# Output.net
KiCad netlist of a schematic drawn in EAGLE
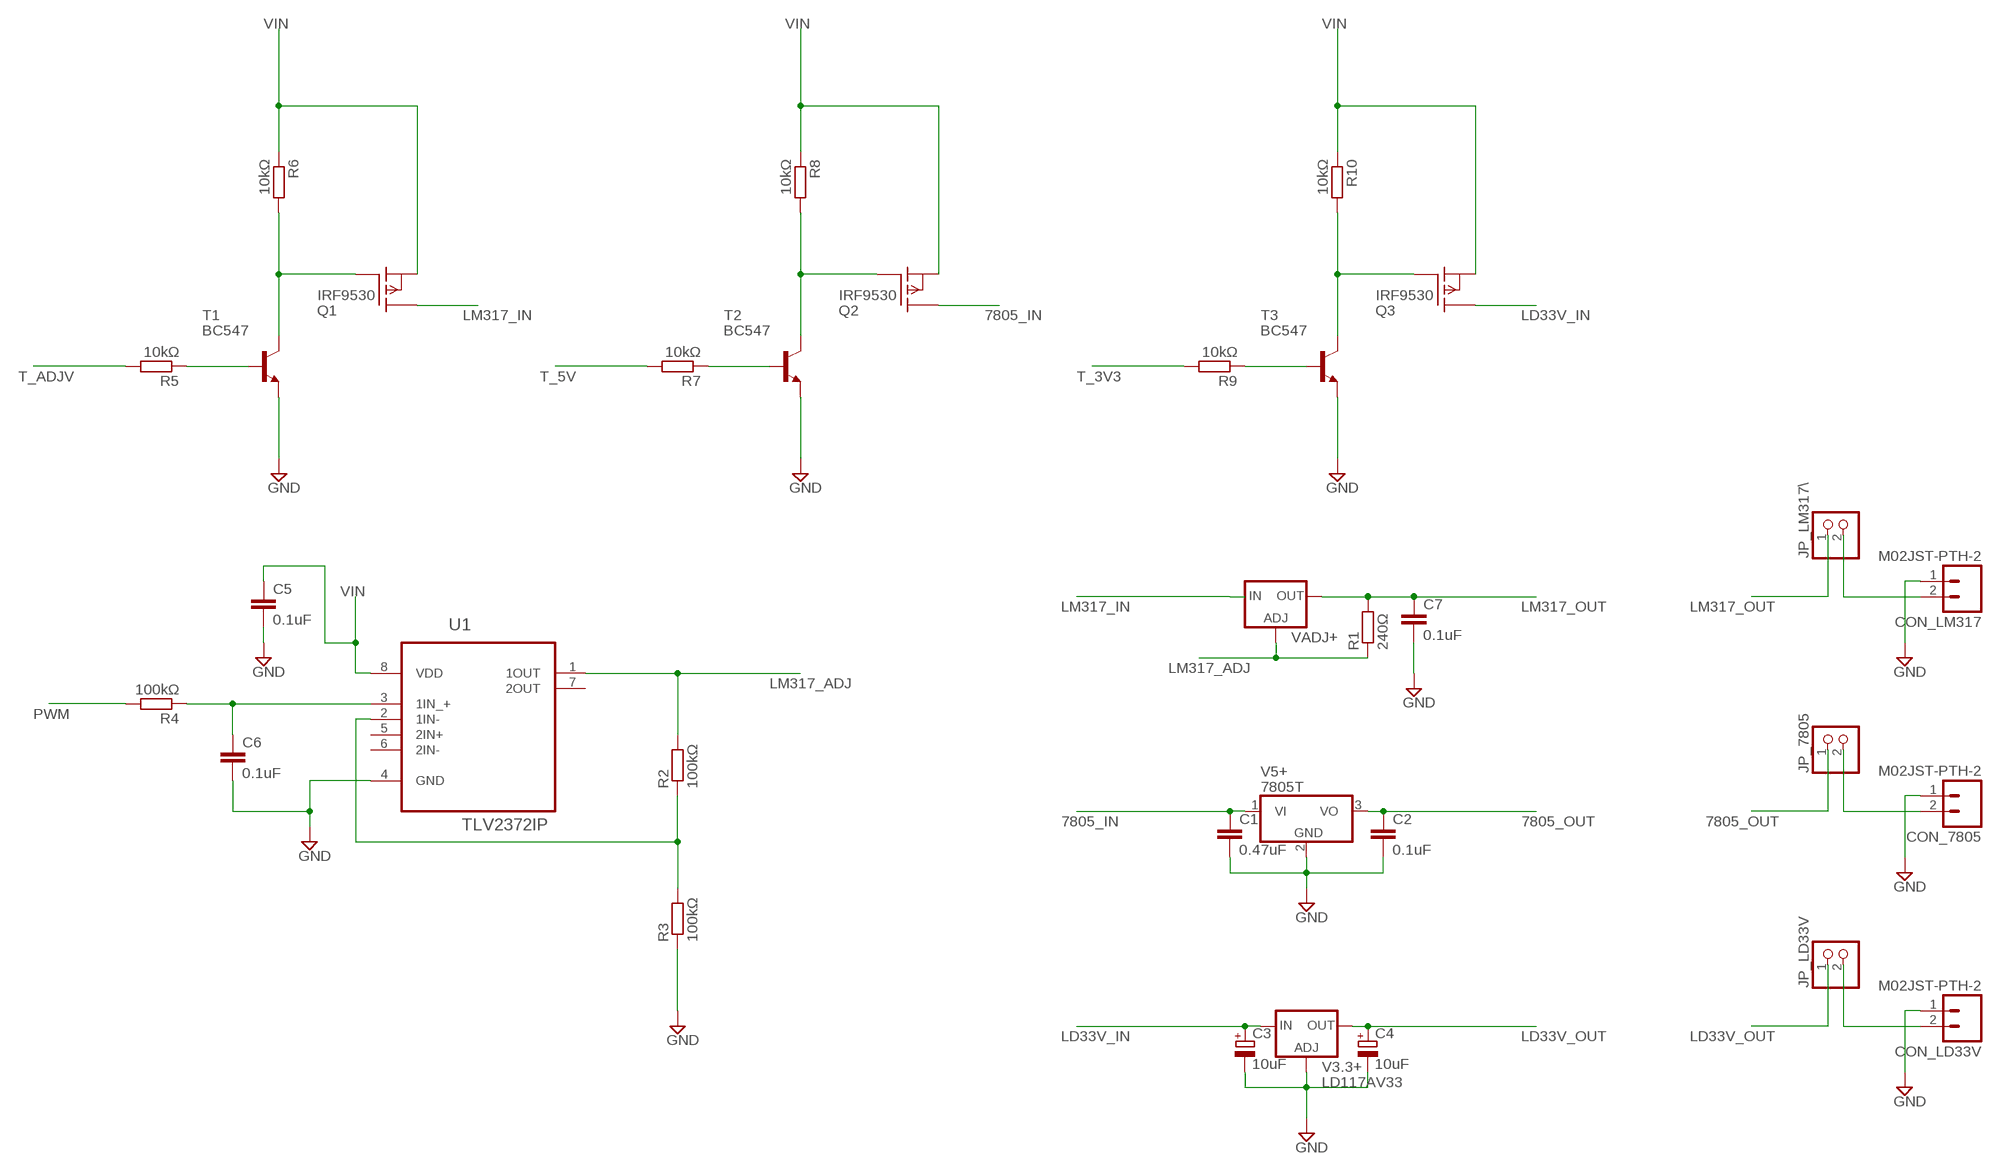
[diagram p0: schematic, sheet 1]

(export (version "E")
  (design (tool "Eeschema 10.0.6"))
  (components
    (comp (ref "C1")
      (value "0.47uF")
      (footprint "eagle-import:C025-025X050")
      (libsource (lib "eagle-import") (part "C-EU025-025X050"))
    )
    (comp (ref "C2")
      (value "0.1uF")
      (footprint "eagle-import:C025-025X050")
      (libsource (lib "eagle-import") (part "C-EU025-025X050"))
    )
    (comp (ref "C3")
      (value "10uF")
      (footprint "eagle-import:E2,5-6")
      (libsource (lib "eagle-import") (part "CPOL-EUE2.5-6"))
    )
    (comp (ref "C4")
      (value "10uF")
      (footprint "eagle-import:E2,5-6")
      (libsource (lib "eagle-import") (part "CPOL-EUE2.5-6"))
    )
    (comp (ref "C5")
      (value "0.1uF")
      (footprint "eagle-import:C025-025X050")
      (libsource (lib "eagle-import") (part "C-EU025-025X050"))
    )
    (comp (ref "C6")
      (value "0.1uF")
      (footprint "eagle-import:C025-025X050")
      (libsource (lib "eagle-import") (part "C-EU025-025X050"))
    )
    (comp (ref "C7")
      (value "0.1uF")
      (footprint "eagle-import:C025-025X050")
      (libsource (lib "eagle-import") (part "C-EU025-025X050"))
    )
    (comp (ref "CON_7805")
      (value "M02JST-PTH-2")
      (footprint "eagle-import:JST-2-PTH")
      (libsource (lib "eagle-import") (part "M02JST-PTH-2"))
    )
    (comp (ref "CON_LD33V")
      (value "M02JST-PTH-2")
      (footprint "eagle-import:JST-2-PTH")
      (libsource (lib "eagle-import") (part "M02JST-PTH-2"))
    )
    (comp (ref "CON_LM317")
      (value "M02JST-PTH-2")
      (footprint "eagle-import:JST-2-PTH")
      (libsource (lib "eagle-import") (part "M02JST-PTH-2"))
    )
    (comp (ref "JP_7805")
      (value "PINHD-1X2")
      (footprint "eagle-import:1X02")
      (libsource (lib "eagle-import") (part "PINHD-1X2"))
    )
    (comp (ref "JP_LD33V")
      (value "PINHD-1X2")
      (footprint "eagle-import:1X02")
      (libsource (lib "eagle-import") (part "PINHD-1X2"))
    )
    (comp (ref "JP_LM317\\")
      (value "PINHD-1X2")
      (footprint "eagle-import:1X02")
      (libsource (lib "eagle-import") (part "PINHD-1X2"))
    )
    (comp (ref "Q1")
      (value "IRF9530")
      (footprint "eagle-import:TO220")
      (libsource (lib "eagle-import") (part "IRF9530"))
    )
    (comp (ref "Q2")
      (value "IRF9530")
      (footprint "eagle-import:TO220")
      (libsource (lib "eagle-import") (part "IRF9530"))
    )
    (comp (ref "Q3")
      (value "IRF9530")
      (footprint "eagle-import:TO220")
      (libsource (lib "eagle-import") (part "IRF9530"))
    )
    (comp (ref "R1")
      (value "240Ω")
      (footprint "eagle-import:0207_10")
      (libsource (lib "eagle-import") (part "R-EU_0207/10"))
    )
    (comp (ref "R2")
      (value "100kΩ")
      (footprint "eagle-import:0207_10")
      (libsource (lib "eagle-import") (part "R-EU_0207/10"))
    )
    (comp (ref "R3")
      (value "100kΩ")
      (footprint "eagle-import:0207_10")
      (libsource (lib "eagle-import") (part "R-EU_0207/10"))
    )
    (comp (ref "R4")
      (value "100kΩ")
      (footprint "eagle-import:0207_10")
      (libsource (lib "eagle-import") (part "R-EU_0207/10"))
    )
    (comp (ref "R5")
      (value "10kΩ")
      (footprint "eagle-import:0207_10")
      (libsource (lib "eagle-import") (part "R-EU_0207/10"))
    )
    (comp (ref "R6")
      (value "10kΩ")
      (footprint "eagle-import:0207_10")
      (libsource (lib "eagle-import") (part "R-EU_0207/10"))
    )
    (comp (ref "R7")
      (value "10kΩ")
      (footprint "eagle-import:0207_10")
      (libsource (lib "eagle-import") (part "R-EU_0207/10"))
    )
    (comp (ref "R8")
      (value "10kΩ")
      (footprint "eagle-import:0207_10")
      (libsource (lib "eagle-import") (part "R-EU_0207/10"))
    )
    (comp (ref "R9")
      (value "10kΩ")
      (footprint "eagle-import:0207_10")
      (libsource (lib "eagle-import") (part "R-EU_0207/10"))
    )
    (comp (ref "R10")
      (value "10kΩ")
      (footprint "eagle-import:0207_10")
      (libsource (lib "eagle-import") (part "R-EU_0207/10"))
    )
    (comp (ref "T1")
      (value "BC547")
      (footprint "eagle-import:TO92")
      (libsource (lib "eagle-import") (part "BC547"))
    )
    (comp (ref "T2")
      (value "BC547")
      (footprint "eagle-import:TO92")
      (libsource (lib "eagle-import") (part "BC547"))
    )
    (comp (ref "T3")
      (value "BC547")
      (footprint "eagle-import:TO92")
      (libsource (lib "eagle-import") (part "BC547"))
    )
    (comp (ref "U1")
      (value "TLV2372IP")
      (footprint "eagle-import:DIP254P762X508-8")
      (libsource (lib "eagle-import") (part "TLV2372IP"))
    )
    (comp (ref "V3.3+")
      (value "LD117AV33")
      (footprint "eagle-import:TO220L1")
      (libsource (lib "eagle-import") (part "LD117A?V33"))
    )
    (comp (ref "V5+")
      (value "7805T")
      (footprint "eagle-import:TO220H")
      (libsource (lib "eagle-import") (part "78T05"))
    )
    (comp (ref "VADJ+")
      (value "LM317TL")
      (footprint "eagle-import:317TL")
      (libsource (lib "eagle-import") (part "LM317TL"))
    )
  )
  (nets
    (net (code "1") (name "/7805_IN") (class "Default")
      (node (ref "C1") (pin "1") (pinfunction "1_1") (pintype "passive"))
      (node (ref "Q2") (pin "2") (pinfunction "D_2") (pintype "passive"))
      (node (ref "V5+") (pin "1") (pinfunction "VI_1") (pintype "input"))
    )
    (net (code "2") (name "/7805_OUT") (class "Default")
      (node (ref "C2") (pin "1") (pinfunction "1_1") (pintype "passive"))
      (node (ref "JP_7805") (pin "1") (pinfunction "1_1") (pintype "passive"))
      (node (ref "V5+") (pin "3") (pinfunction "VO_3") (pintype "passive"))
    )
    (net (code "3") (name "/LD33V_IN") (class "Default")
      (node (ref "C3") (pin "+") (pinfunction "+_+") (pintype "passive"))
      (node (ref "Q3") (pin "2") (pinfunction "D_2") (pintype "passive"))
      (node (ref "V3.3+") (pin "3") (pinfunction "IN_3") (pintype "input"))
    )
    (net (code "4") (name "/LD33V_OUT") (class "Default")
      (node (ref "C4") (pin "+") (pinfunction "+_+") (pintype "passive"))
      (node (ref "JP_LD33V") (pin "1") (pinfunction "1_1") (pintype "passive"))
      (node (ref "V3.3+") (pin "2") (pinfunction "OUT_2") (pintype "passive"))
    )
    (net (code "5") (name "/LM317_ADJ") (class "Default")
      (node (ref "R1") (pin "1") (pinfunction "1_1") (pintype "passive"))
      (node (ref "R2") (pin "2") (pinfunction "2_2") (pintype "passive"))
      (node (ref "U1") (pin "1") (pinfunction "1OUT_1") (pintype "output"))
      (node (ref "VADJ+") (pin "1") (pinfunction "ADJ_1") (pintype "input"))
    )
    (net (code "6") (name "/LM317_IN") (class "Default")
      (node (ref "Q1") (pin "2") (pinfunction "D_2") (pintype "passive"))
      (node (ref "VADJ+") (pin "3") (pinfunction "IN_3") (pintype "input"))
    )
    (net (code "7") (name "/LM317_OUT") (class "Default")
      (node (ref "C7") (pin "1") (pinfunction "1_1") (pintype "passive"))
      (node (ref "JP_LM317\\") (pin "1") (pinfunction "1_1") (pintype "passive"))
      (node (ref "R1") (pin "2") (pinfunction "2_2") (pintype "passive"))
      (node (ref "VADJ+") (pin "2") (pinfunction "OUT_2") (pintype "passive"))
    )
    (net (code "8") (name "/PWM") (class "Default")
      (node (ref "R4") (pin "2") (pinfunction "2_2") (pintype "passive"))
    )
    (net (code "9") (name "/T_3V3") (class "Default")
      (node (ref "R9") (pin "2") (pinfunction "2_2") (pintype "passive"))
    )
    (net (code "10") (name "/T_5V") (class "Default")
      (node (ref "R7") (pin "2") (pinfunction "2_2") (pintype "passive"))
    )
    (net (code "11") (name "/T_ADJV") (class "Default")
      (node (ref "R5") (pin "2") (pinfunction "2_2") (pintype "passive"))
    )
    (net (code "12") (name "/VIN") (class "Default")
      (node (ref "C5") (pin "1") (pinfunction "1_1") (pintype "passive"))
      (node (ref "Q1") (pin "3") (pinfunction "S_3") (pintype "passive"))
      (node (ref "Q2") (pin "3") (pinfunction "S_3") (pintype "passive"))
      (node (ref "Q3") (pin "3") (pinfunction "S_3") (pintype "passive"))
      (node (ref "R10") (pin "1") (pinfunction "1_1") (pintype "passive"))
      (node (ref "R6") (pin "1") (pinfunction "1_1") (pintype "passive"))
      (node (ref "R8") (pin "1") (pinfunction "1_1") (pintype "passive"))
      (node (ref "U1") (pin "8") (pinfunction "VDD_8") (pintype "power_in"))
    )
    (net (code "13") (name "GND") (class "Default")
      (node (ref "C1") (pin "2") (pinfunction "2_2") (pintype "passive"))
      (node (ref "C2") (pin "2") (pinfunction "2_2") (pintype "passive"))
      (node (ref "C3") (pin "-") (pinfunction "-_-") (pintype "passive"))
      (node (ref "C4") (pin "-") (pinfunction "-_-") (pintype "passive"))
      (node (ref "C5") (pin "2") (pinfunction "2_2") (pintype "passive"))
      (node (ref "C6") (pin "2") (pinfunction "2_2") (pintype "passive"))
      (node (ref "C7") (pin "2") (pinfunction "2_2") (pintype "passive"))
      (node (ref "CON_7805") (pin "1") (pinfunction "1_1") (pintype "passive"))
      (node (ref "CON_LD33V") (pin "1") (pinfunction "1_1") (pintype "passive"))
      (node (ref "CON_LM317") (pin "1") (pinfunction "1_1") (pintype "passive"))
      (node (ref "R3") (pin "1") (pinfunction "1_1") (pintype "passive"))
      (node (ref "T1") (pin "1") (pinfunction "E_1") (pintype "passive"))
      (node (ref "T2") (pin "1") (pinfunction "E_1") (pintype "passive"))
      (node (ref "T3") (pin "1") (pinfunction "E_1") (pintype "passive"))
      (node (ref "U1") (pin "4") (pinfunction "GND_4") (pintype "passive"))
      (node (ref "V3.3+") (pin "1") (pinfunction "ADJ_1") (pintype "input"))
      (node (ref "V5+") (pin "2") (pinfunction "GND_2") (pintype "passive"))
    )
    (net (code "14") (name "Net-(CON_7805-Pad2)") (class "Default")
      (node (ref "CON_7805") (pin "2") (pinfunction "2_2") (pintype "passive"))
      (node (ref "JP_7805") (pin "2") (pinfunction "2_2") (pintype "passive"))
    )
    (net (code "15") (name "Net-(CON_LD33V-Pad2)") (class "Default")
      (node (ref "CON_LD33V") (pin "2") (pinfunction "2_2") (pintype "passive"))
      (node (ref "JP_LD33V") (pin "2") (pinfunction "2_2") (pintype "passive"))
    )
    (net (code "16") (name "Net-(CON_LM317-Pad2)") (class "Default")
      (node (ref "CON_LM317") (pin "2") (pinfunction "2_2") (pintype "passive"))
      (node (ref "JP_LM317\\") (pin "2") (pinfunction "2_2") (pintype "passive"))
    )
    (net (code "17") (name "Net-(Q1-G)") (class "Default")
      (node (ref "Q1") (pin "1") (pinfunction "G_1") (pintype "passive"))
      (node (ref "R6") (pin "2") (pinfunction "2_2") (pintype "passive"))
      (node (ref "T1") (pin "3") (pinfunction "C_3") (pintype "passive"))
    )
    (net (code "18") (name "Net-(Q2-G)") (class "Default")
      (node (ref "Q2") (pin "1") (pinfunction "G_1") (pintype "passive"))
      (node (ref "R8") (pin "2") (pinfunction "2_2") (pintype "passive"))
      (node (ref "T2") (pin "3") (pinfunction "C_3") (pintype "passive"))
    )
    (net (code "19") (name "Net-(Q3-G)") (class "Default")
      (node (ref "Q3") (pin "1") (pinfunction "G_1") (pintype "passive"))
      (node (ref "R10") (pin "2") (pinfunction "2_2") (pintype "passive"))
      (node (ref "T3") (pin "3") (pinfunction "C_3") (pintype "passive"))
    )
    (net (code "20") (name "Net-(T1-B)") (class "Default")
      (node (ref "R5") (pin "1") (pinfunction "1_1") (pintype "passive"))
      (node (ref "T1") (pin "2") (pinfunction "B_2") (pintype "passive"))
    )
    (net (code "21") (name "Net-(T2-B)") (class "Default")
      (node (ref "R7") (pin "1") (pinfunction "1_1") (pintype "passive"))
      (node (ref "T2") (pin "2") (pinfunction "B_2") (pintype "passive"))
    )
    (net (code "22") (name "Net-(T3-B)") (class "Default")
      (node (ref "R9") (pin "1") (pinfunction "1_1") (pintype "passive"))
      (node (ref "T3") (pin "2") (pinfunction "B_2") (pintype "passive"))
    )
    (net (code "23") (name "Net-(U1-1IN-)") (class "Default")
      (node (ref "R2") (pin "1") (pinfunction "1_1") (pintype "passive"))
      (node (ref "R3") (pin "2") (pinfunction "2_2") (pintype "passive"))
      (node (ref "U1") (pin "2") (pinfunction "1IN-_2") (pintype "input"))
    )
    (net (code "24") (name "Net-(U1-1IN_+)") (class "Default")
      (node (ref "C6") (pin "1") (pinfunction "1_1") (pintype "passive"))
      (node (ref "R4") (pin "1") (pinfunction "1_1") (pintype "passive"))
      (node (ref "U1") (pin "3") (pinfunction "1IN_+_3") (pintype "input"))
    )
    (net (code "25") (name "unconnected-(U1-2IN+-Pad5)") (class "Default")
      (node (ref "U1") (pin "5") (pinfunction "2IN+_5") (pintype "input"))
    )
    (net (code "26") (name "unconnected-(U1-2IN--Pad6)") (class "Default")
      (node (ref "U1") (pin "6") (pinfunction "2IN-_6") (pintype "input"))
    )
    (net (code "27") (name "unconnected-(U1-2OUT-Pad7)") (class "Default")
      (node (ref "U1") (pin "7") (pinfunction "2OUT_7") (pintype "output"))
    )
  )
)
